# Nixie_3.net
KiCad netlist of a schematic drawn in Altium Designer
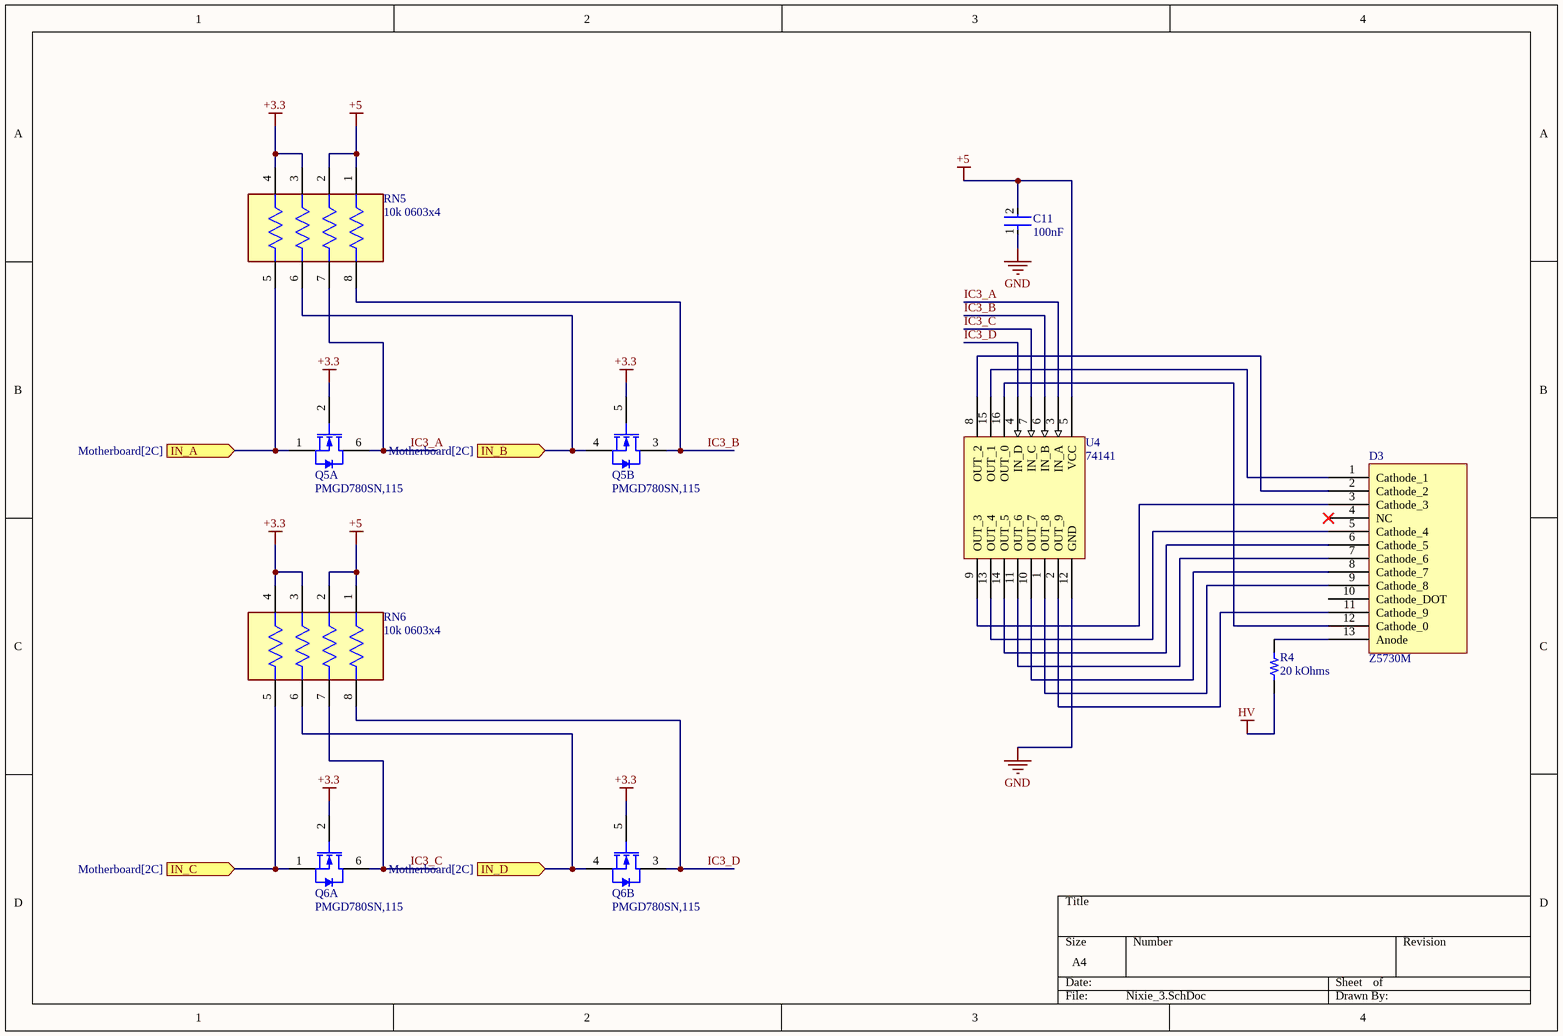
[diagram p0: Nixie_3.SchDoc]

(export (version "E")
  (design (tool "Eeschema 10.0.6"))
  (components
    (comp (ref "C11")
      (value "100nF")
      (footprint "FP-C1005-050-0_15-MFG")
      (description "CAP CER 100nF 10V X5R 0402")
      (fields (field (name "TOLERANCE") "20%") (field (name "VOLTAGE") "10V"))
      (libsource (lib "Altium Content Vault") (part "11868f565c42a9108669ba33697ecf6"))
    )
    (comp (ref "D3") (value "Z5730M") (footprint "Z5730M") (libsource (lib "Z5730M") (part "Z5730M")))
    (comp (ref "Q5")
      (value "PMGD780SN,115")
      (footprint "NXP-SOT363_N")
      (description "Dual N-Channel uTrenchMOS Standard Level FET, 60 V, 0.49 A, 6-Pin SOT363, Tape and Reel")
      (fields (field (name "MANUFACTURER") "NXP Semiconductors"))
      (libsource (lib "Altium Content Vault") (part "NXP-NNMOS-SGDSGD-6_B"))
    )
    (comp (ref "Q6")
      (value "PMGD780SN,115")
      (footprint "NXP-SOT363_N")
      (description "Dual N-Channel uTrenchMOS Standard Level FET, 60 V, 0.49 A, 6-Pin SOT363, Tape and Reel")
      (fields (field (name "MANUFACTURER") "NXP Semiconductors"))
      (libsource (lib "Altium Content Vault") (part "NXP-NNMOS-SGDSGD-6_B"))
    )
    (comp (ref "R4")
      (value "20 kOhms")
      (footprint "RES 1210_3225")
      (description "RES SMD 20K OHM 1% 3/4W 1210")
      (fields (field (name "PART NUMBER") "CRCW121020K0FKEAHP") (field (name "MANUFACTURER") "Vishay Dale"))
      (libsource (lib "Celestial Altium Library - altium_library") (part "Resistor"))
    )
    (comp (ref "RN5")
      (value "10k 0603x4")
      (footprint "FP-EXB38V-MFG")
      (description "RES ARRAY 4 RES 10K OHM 1206\r\nRC-ML08W103JT")
      (fields (field (name "TOLERANCE") "5%"))
      (libsource (lib "Altium Content Vault") (part "2ca08171d0bbdee8be62227dae509d7"))
    )
    (comp (ref "RN6")
      (value "10k 0603x4")
      (footprint "FP-EXB38V-MFG")
      (description "RES ARRAY 4 RES 10K OHM 1206\r\nRC-ML08W103JT")
      (fields (field (name "TOLERANCE") "5%"))
      (libsource (lib "Altium Content Vault") (part "2ca08171d0bbdee8be62227dae509d7"))
    )
    (comp (ref "U4") (value "74141") (footprint "DIP-16") (libsource (lib "Z5730M") (part "74141")))
  )
  (nets
    (net (code "1") (name "+3.3") (class "Default")
      (node (ref "Q5") (pin "2") (pinfunction "G1_2") (pintype "passive"))
      (node (ref "Q5") (pin "5") (pinfunction "G2_5") (pintype "passive"))
      (node (ref "Q6") (pin "2") (pinfunction "G1_2") (pintype "passive"))
      (node (ref "Q6") (pin "5") (pinfunction "G2_5") (pintype "passive"))
      (node (ref "RN5") (pin "3") (pinfunction "3_3") (pintype "passive"))
      (node (ref "RN5") (pin "4") (pinfunction "4_4") (pintype "passive"))
      (node (ref "RN6") (pin "3") (pinfunction "3_3") (pintype "passive"))
      (node (ref "RN6") (pin "4") (pinfunction "4_4") (pintype "passive"))
    )
    (net (code "2") (name "+5") (class "Default")
      (node (ref "C11") (pin "2") (pinfunction "2_2") (pintype "passive"))
      (node (ref "RN5") (pin "1") (pinfunction "1_1") (pintype "passive"))
      (node (ref "RN5") (pin "2") (pinfunction "2_2") (pintype "passive"))
      (node (ref "RN6") (pin "1") (pinfunction "1_1") (pintype "passive"))
      (node (ref "RN6") (pin "2") (pinfunction "2_2") (pintype "passive"))
      (node (ref "U4") (pin "5") (pinfunction "VCC_5") (pintype "power_in"))
    )
    (net (code "3") (name "/IC3_A") (class "Default")
      (node (ref "Q5") (pin "6") (pinfunction "D1_6") (pintype "passive"))
      (node (ref "RN5") (pin "7") (pinfunction "7_7") (pintype "passive"))
      (node (ref "U4") (pin "3") (pinfunction "IN_A_3") (pintype "input"))
    )
    (net (code "4") (name "/IC3_B") (class "Default")
      (node (ref "Q5") (pin "3") (pinfunction "D2_3") (pintype "passive"))
      (node (ref "RN5") (pin "8") (pinfunction "8_8") (pintype "passive"))
      (node (ref "U4") (pin "6") (pinfunction "IN_B_6") (pintype "input"))
    )
    (net (code "5") (name "/IC3_C") (class "Default")
      (node (ref "Q6") (pin "6") (pinfunction "D1_6") (pintype "passive"))
      (node (ref "RN6") (pin "7") (pinfunction "7_7") (pintype "passive"))
      (node (ref "U4") (pin "7") (pinfunction "IN_C_7") (pintype "input"))
    )
    (net (code "6") (name "/IC3_D") (class "Default")
      (node (ref "Q6") (pin "3") (pinfunction "D2_3") (pintype "passive"))
      (node (ref "RN6") (pin "8") (pinfunction "8_8") (pintype "passive"))
      (node (ref "U4") (pin "4") (pinfunction "IN_D_4") (pintype "input"))
    )
    (net (code "7") (name "/IN_A") (class "Default")
      (node (ref "Q5") (pin "1") (pinfunction "S1_1") (pintype "passive"))
      (node (ref "RN5") (pin "5") (pinfunction "5_5") (pintype "passive"))
    )
    (net (code "8") (name "/IN_B") (class "Default")
      (node (ref "Q5") (pin "4") (pinfunction "S2_4") (pintype "passive"))
      (node (ref "RN5") (pin "6") (pinfunction "6_6") (pintype "passive"))
    )
    (net (code "9") (name "/IN_C") (class "Default")
      (node (ref "Q6") (pin "1") (pinfunction "S1_1") (pintype "passive"))
      (node (ref "RN6") (pin "5") (pinfunction "5_5") (pintype "passive"))
    )
    (net (code "10") (name "/IN_D") (class "Default")
      (node (ref "Q6") (pin "4") (pinfunction "S2_4") (pintype "passive"))
      (node (ref "RN6") (pin "6") (pinfunction "6_6") (pintype "passive"))
    )
    (net (code "11") (name "GND") (class "Default")
      (node (ref "C11") (pin "1") (pinfunction "1_1") (pintype "passive"))
      (node (ref "U4") (pin "12") (pinfunction "GND_12") (pintype "power_in"))
    )
    (net (code "12") (name "HV") (class "Default")
      (node (ref "R4") (pin "1") (pinfunction "1_1") (pintype "passive"))
    )
    (net (code "13") (name "Net-(D3-Anode)") (class "Default")
      (node (ref "D3") (pin "13") (pinfunction "Anode_13") (pintype "passive"))
      (node (ref "R4") (pin "2") (pinfunction "2_2") (pintype "passive"))
    )
    (net (code "14") (name "Net-(D3-Cathode_0)") (class "Default")
      (node (ref "D3") (pin "12") (pinfunction "Cathode_0_12") (pintype "passive"))
      (node (ref "U4") (pin "16") (pinfunction "OUT_0_16") (pintype "open_collector"))
    )
    (net (code "15") (name "Net-(D3-Cathode_1)") (class "Default")
      (node (ref "D3") (pin "1") (pinfunction "Cathode_1_1") (pintype "passive"))
      (node (ref "U4") (pin "15") (pinfunction "OUT_1_15") (pintype "open_collector"))
    )
    (net (code "16") (name "Net-(D3-Cathode_2)") (class "Default")
      (node (ref "D3") (pin "2") (pinfunction "Cathode_2_2") (pintype "passive"))
      (node (ref "U4") (pin "8") (pinfunction "OUT_2_8") (pintype "open_collector"))
    )
    (net (code "17") (name "Net-(D3-Cathode_3)") (class "Default")
      (node (ref "D3") (pin "3") (pinfunction "Cathode_3_3") (pintype "passive"))
      (node (ref "U4") (pin "9") (pinfunction "OUT_3_9") (pintype "open_collector"))
    )
    (net (code "18") (name "Net-(D3-Cathode_4)") (class "Default")
      (node (ref "D3") (pin "5") (pinfunction "Cathode_4_5") (pintype "passive"))
      (node (ref "U4") (pin "13") (pinfunction "OUT_4_13") (pintype "open_collector"))
    )
    (net (code "19") (name "Net-(D3-Cathode_5)") (class "Default")
      (node (ref "D3") (pin "6") (pinfunction "Cathode_5_6") (pintype "passive"))
      (node (ref "U4") (pin "14") (pinfunction "OUT_5_14") (pintype "open_collector"))
    )
    (net (code "20") (name "Net-(D3-Cathode_6)") (class "Default")
      (node (ref "D3") (pin "7") (pinfunction "Cathode_6_7") (pintype "passive"))
      (node (ref "U4") (pin "11") (pinfunction "OUT_6_11") (pintype "open_collector"))
    )
    (net (code "21") (name "Net-(D3-Cathode_7)") (class "Default")
      (node (ref "D3") (pin "8") (pinfunction "Cathode_7_8") (pintype "passive"))
      (node (ref "U4") (pin "10") (pinfunction "OUT_7_10") (pintype "open_collector"))
    )
    (net (code "22") (name "Net-(D3-Cathode_8)") (class "Default")
      (node (ref "D3") (pin "9") (pinfunction "Cathode_8_9") (pintype "passive"))
      (node (ref "U4") (pin "1") (pinfunction "OUT_8_1") (pintype "open_collector"))
    )
    (net (code "23") (name "Net-(D3-Cathode_9)") (class "Default")
      (node (ref "D3") (pin "11") (pinfunction "Cathode_9_11") (pintype "passive"))
      (node (ref "U4") (pin "2") (pinfunction "OUT_9_2") (pintype "open_collector"))
    )
    (net (code "24") (name "unconnected-(D3-Cathode_DOT-Pad10)") (class "Default")
      (node (ref "D3") (pin "10") (pinfunction "Cathode_DOT_10") (pintype "passive"))
    )
    (net (code "25") (name "unconnected-(D3-NC-Pad4)") (class "Default")
      (node (ref "D3") (pin "4") (pinfunction "NC_4") (pintype "passive+no_connect"))
    )
  )
)
